# esp-lis3dh.net
KiCad netlist of a schematic drawn in EAGLE
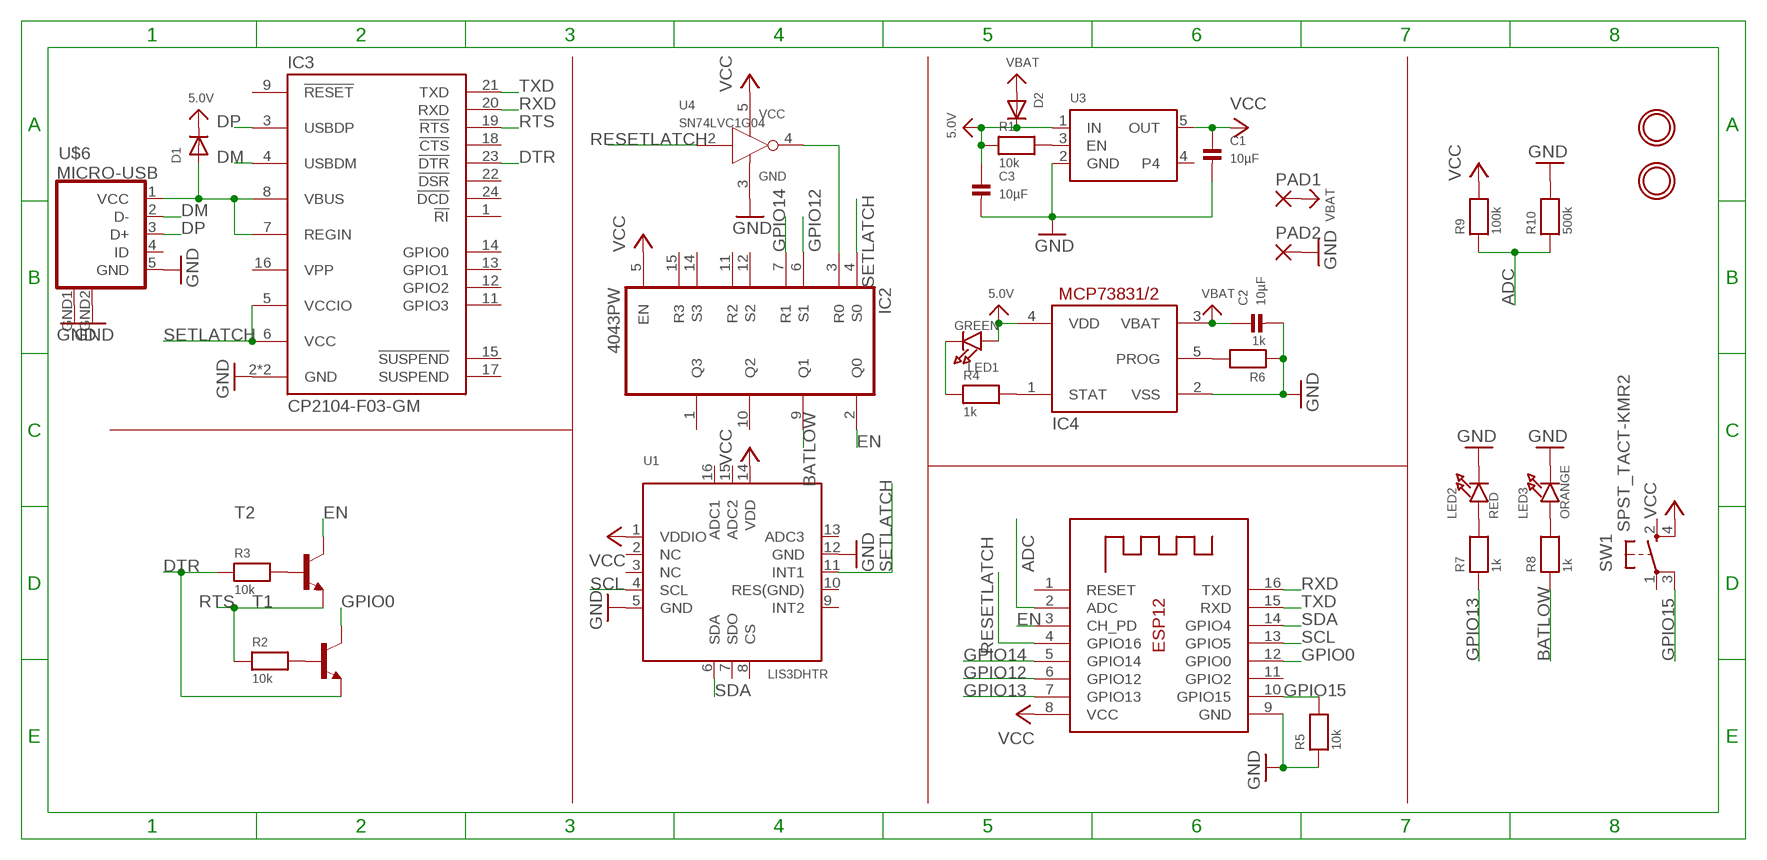
[diagram p0: schematic, sheet 1]

(export (version "E")
  (design (tool "Eeschema 10.0.6"))
  (components
    (comp (ref "C1")
      (value "10µF")
      (footprint "eagle-import:0805")
      (libsource (lib "eagle-import") (part "CAP_CERAMIC0805"))
    )
    (comp (ref "C2")
      (value "10µF")
      (footprint "eagle-import:0805")
      (libsource (lib "eagle-import") (part "CAP_CERAMIC0805"))
    )
    (comp (ref "C3")
      (value "10µF")
      (footprint "eagle-import:0805")
      (libsource (lib "eagle-import") (part "CAP_CERAMIC0805"))
    )
    (comp (ref "D1")
      (value "DIODESOD-123")
      (footprint "eagle-import:SOD-123")
      (libsource (lib "eagle-import") (part "DIODESOD-123"))
    )
    (comp (ref "D2")
      (value "DIODESOD-123")
      (footprint "eagle-import:SOD-123")
      (libsource (lib "eagle-import") (part "DIODESOD-123"))
    )
    (comp (ref "IC2")
      (value "4043PW")
      (footprint "eagle-import:TSSOP16")
      (libsource (lib "eagle-import") (part "4043PW"))
    )
    (comp (ref "IC3")
      (value "CP2104-F03-GM")
      (footprint "eagle-import:QFN24-PAD")
      (fields (field (name "MF") "Silicon Labs") (field (name "MP") "CP2104"))
      (libsource (lib "eagle-import") (part "CP2104-F03-GM"))
    )
    (comp (ref "IC4")
      (value "MCP73831/OT")
      (footprint "eagle-import:SOT23-5L")
      (libsource (lib "eagle-import") (part "MCP73831/OT"))
    )
    (comp (ref "LED1")
      (value "GREEN")
      (footprint "eagle-import:CHIPLED_0805")
      (libsource (lib "eagle-import") (part "LED0805"))
    )
    (comp (ref "LED2")
      (value "RED")
      (footprint "eagle-import:CHIPLED_0805")
      (libsource (lib "eagle-import") (part "LED0805"))
    )
    (comp (ref "LED3")
      (value "ORANGE")
      (footprint "eagle-import:CHIPLED_0805")
      (libsource (lib "eagle-import") (part "LED0805"))
    )
    (comp (ref "PAD1")
      (value "SMD2")
      (footprint "eagle-import:SMD1,27-2,54")
      (libsource (lib "eagle-import") (part "SMD2"))
    )
    (comp (ref "PAD2")
      (value "SMD2")
      (footprint "eagle-import:SMD1,27-2,54")
      (libsource (lib "eagle-import") (part "SMD2"))
    )
    (comp (ref "R1")
      (value "10k")
      (footprint "eagle-import:0603")
      (libsource (lib "eagle-import") (part "RESISTOR0603"))
    )
    (comp (ref "R2")
      (value "10k")
      (footprint "eagle-import:0603")
      (libsource (lib "eagle-import") (part "RESISTOR0603"))
    )
    (comp (ref "R3")
      (value "10k")
      (footprint "eagle-import:0603")
      (libsource (lib "eagle-import") (part "RESISTOR0603"))
    )
    (comp (ref "R4")
      (value "1k")
      (footprint "eagle-import:0603")
      (libsource (lib "eagle-import") (part "RESISTOR0603"))
    )
    (comp (ref "R5")
      (value "10k")
      (footprint "eagle-import:0603")
      (libsource (lib "eagle-import") (part "RESISTOR0603"))
    )
    (comp (ref "R6")
      (value "1k")
      (footprint "eagle-import:0603")
      (libsource (lib "eagle-import") (part "RESISTOR0603"))
    )
    (comp (ref "R7")
      (value "1k")
      (footprint "eagle-import:0603")
      (libsource (lib "eagle-import") (part "RESISTOR0603"))
    )
    (comp (ref "R8")
      (value "1k")
      (footprint "eagle-import:0603")
      (libsource (lib "eagle-import") (part "RESISTOR0603"))
    )
    (comp (ref "R9")
      (value "100k")
      (footprint "eagle-import:0603")
      (libsource (lib "eagle-import") (part "RESISTOR0603"))
    )
    (comp (ref "R10")
      (value "500k")
      (footprint "eagle-import:0603")
      (libsource (lib "eagle-import") (part "RESISTOR0603"))
    )
    (comp (ref "SW1")
      (value "SPST_TACT-KMR2")
      (footprint "eagle-import:KMR2")
      (libsource (lib "eagle-import") (part "SPST_TACT-KMR2"))
    )
    (comp (ref "T1")
      (value "MMBT2222ALT1-NPN-SOT23-BEC")
      (footprint "eagle-import:SOT23-BEC")
      (libsource (lib "eagle-import") (part "-NPN-SOT23-BECMMBT2222ALT1"))
    )
    (comp (ref "T2")
      (value "MMBT2222ALT1-NPN-SOT23-BEC")
      (footprint "eagle-import:SOT23-BEC")
      (libsource (lib "eagle-import") (part "-NPN-SOT23-BECMMBT2222ALT1"))
    )
    (comp (ref "U$6")
      (value "MICRO-USB")
      (footprint "eagle-import:MICRO-USB")
      (libsource (lib "eagle-import") (part "MICRO-USB"))
    )
    (comp (ref "U$7")
      (value "MOUNTINGHOLE2.5")
      (footprint "eagle-import:MOUNTINGHOLE_2.5_PLATED")
      (libsource (lib "eagle-import") (part "MOUNTINGHOLE2.5"))
    )
    (comp (ref "U$8")
      (value "MOUNTINGHOLE2.5")
      (footprint "eagle-import:MOUNTINGHOLE_2.5_PLATED")
      (libsource (lib "eagle-import") (part "MOUNTINGHOLE2.5"))
    )
    (comp (ref "U1")
      (value "LIS3DHTR")
      (footprint "eagle-import:LGA16_3X3MM")
      (libsource (lib "eagle-import") (part "ACCEL_LIS3DHTR"))
    )
    (comp (ref "U3")
      (value "VREG_SOT23-5")
      (footprint "eagle-import:SOT23-5")
      (libsource (lib "eagle-import") (part "VREG_SOT23-5"))
    )
    (comp (ref "U4")
      (value "SN74LVC1G04")
      (footprint "eagle-import:SOT23-5")
      (libsource (lib "eagle-import") (part "SN74LVC1G04"))
    )
    (comp (ref "X1")
      (value "ESP-12")
      (footprint "eagle-import:ESP-12")
      (libsource (lib "eagle-import") (part "ESP-12"))
    )
  )
  (nets
    (net (code "1") (name "/ADC") (class "Default")
      (node (ref "R10") (pin "1") (pinfunction "1_1") (pintype "passive"))
      (node (ref "R9") (pin "1") (pinfunction "1_1") (pintype "passive"))
      (node (ref "X1") (pin "2") (pinfunction "ADC_2") (pintype "passive"))
    )
    (net (code "2") (name "/BATLOW") (class "Default")
      (node (ref "IC2") (pin "9") (pinfunction "Q1_9") (pintype "output"))
      (node (ref "R8") (pin "1") (pinfunction "1_1") (pintype "passive"))
    )
    (net (code "3") (name "/DM") (class "Default")
      (node (ref "IC3") (pin "4") (pinfunction "USBDM_4") (pintype "bidirectional"))
      (node (ref "U$6") (pin "2") (pinfunction "D-_2") (pintype "bidirectional"))
    )
    (net (code "4") (name "/DP") (class "Default")
      (node (ref "IC3") (pin "3") (pinfunction "USBDP_3") (pintype "bidirectional"))
      (node (ref "U$6") (pin "3") (pinfunction "D+_3") (pintype "bidirectional"))
    )
    (net (code "5") (name "/DTR") (class "Default")
      (node (ref "IC3") (pin "23") (pinfunction "~{DTR}_23") (pintype "bidirectional"))
      (node (ref "R3") (pin "1") (pinfunction "1_1") (pintype "passive"))
      (node (ref "T1") (pin "E") (pinfunction "E_E") (pintype "passive"))
    )
    (net (code "6") (name "/EN") (class "Default")
      (node (ref "IC2") (pin "2") (pinfunction "Q0_2") (pintype "output"))
      (node (ref "T2") (pin "C") (pinfunction "C_C") (pintype "passive"))
      (node (ref "X1") (pin "3") (pinfunction "CH_PD_3") (pintype "input"))
    )
    (net (code "7") (name "/GPIO0") (class "Default")
      (node (ref "T1") (pin "C") (pinfunction "C_C") (pintype "passive"))
      (node (ref "X1") (pin "12") (pinfunction "GPIO0_12") (pintype "bidirectional"))
    )
    (net (code "8") (name "/GPIO12") (class "Default")
      (node (ref "IC2") (pin "6") (pinfunction "S1_6") (pintype "input"))
      (node (ref "X1") (pin "6") (pinfunction "GPIO12_6") (pintype "bidirectional"))
    )
    (net (code "9") (name "/GPIO13") (class "Default")
      (node (ref "R7") (pin "1") (pinfunction "1_1") (pintype "passive"))
      (node (ref "X1") (pin "7") (pinfunction "GPIO13_7") (pintype "bidirectional"))
    )
    (net (code "10") (name "/GPIO14") (class "Default")
      (node (ref "IC2") (pin "7") (pinfunction "R1_7") (pintype "input"))
      (node (ref "X1") (pin "5") (pinfunction "GPIO14_5") (pintype "bidirectional"))
    )
    (net (code "11") (name "/GPIO15") (class "Default")
      (node (ref "R5") (pin "2") (pinfunction "2_2") (pintype "passive"))
      (node (ref "SW1") (pin "3") (pinfunction "P1_3") (pintype "passive"))
      (node (ref "X1") (pin "10") (pinfunction "GPIO15_10") (pintype "bidirectional"))
    )
    (net (code "12") (name "/RESETLATCH") (class "Default")
      (node (ref "U4") (pin "2") (pinfunction "A_2") (pintype "bidirectional"))
      (node (ref "X1") (pin "4") (pinfunction "GPIO16_4") (pintype "bidirectional"))
    )
    (net (code "13") (name "/RTS") (class "Default")
      (node (ref "IC3") (pin "19") (pinfunction "~{RTS}_19") (pintype "bidirectional"))
      (node (ref "R2") (pin "1") (pinfunction "1_1") (pintype "passive"))
      (node (ref "T2") (pin "E") (pinfunction "E_E") (pintype "passive"))
    )
    (net (code "14") (name "/RXD") (class "Default")
      (node (ref "IC3") (pin "20") (pinfunction "RXD_20") (pintype "bidirectional"))
      (node (ref "X1") (pin "16") (pinfunction "TXD_16") (pintype "output"))
    )
    (net (code "15") (name "/SCL") (class "Default")
      (node (ref "U1") (pin "4") (pinfunction "SCL_4") (pintype "bidirectional"))
      (node (ref "X1") (pin "13") (pinfunction "GPIO5_13") (pintype "bidirectional"))
    )
    (net (code "16") (name "/SDA") (class "Default")
      (node (ref "U1") (pin "6") (pinfunction "SDA_6") (pintype "bidirectional"))
      (node (ref "X1") (pin "14") (pinfunction "GPIO4_14") (pintype "bidirectional"))
    )
    (net (code "17") (name "/SETLATCH") (class "Default")
      (node (ref "IC2") (pin "4") (pinfunction "S0_4") (pintype "input"))
      (node (ref "IC3") (pin "5") (pinfunction "VCCIO_5") (pintype "power_in"))
      (node (ref "IC3") (pin "6") (pinfunction "VCC_6") (pintype "power_in"))
      (node (ref "U1") (pin "11") (pinfunction "INT1_11") (pintype "output"))
    )
    (net (code "18") (name "/TXD") (class "Default")
      (node (ref "IC3") (pin "21") (pinfunction "TXD_21") (pintype "bidirectional"))
      (node (ref "X1") (pin "15") (pinfunction "RXD_15") (pintype "input"))
    )
    (net (code "19") (name "/VPP") (class "Default")
      (node (ref "IC3") (pin "16") (pinfunction "VPP_16") (pintype "power_in"))
    )
    (net (code "20") (name "5.0V") (class "Default")
      (node (ref "C3") (pin "1") (pinfunction "P$1_1") (pintype "passive"))
      (node (ref "D1") (pin "C") (pinfunction "C_C") (pintype "passive"))
      (node (ref "D2") (pin "C") (pinfunction "C_C") (pintype "passive"))
      (node (ref "IC4") (pin "4") (pinfunction "VDD_4") (pintype "power_in"))
      (node (ref "LED1") (pin "A") (pinfunction "A_A") (pintype "passive"))
      (node (ref "R1") (pin "1") (pinfunction "1_1") (pintype "passive"))
      (node (ref "U3") (pin "1") (pinfunction "IN_1") (pintype "bidirectional"))
    )
    (net (code "21") (name "GND") (class "Default")
      (node (ref "C1") (pin "2") (pinfunction "P$2_2") (pintype "passive"))
      (node (ref "C2") (pin "2") (pinfunction "P$2_2") (pintype "passive"))
      (node (ref "C3") (pin "2") (pinfunction "P$2_2") (pintype "passive"))
      (node (ref "IC3") (pin "2") (pinfunction "GND_2") (pintype "power_in"))
      (node (ref "IC3") (pin "TP") (pinfunction "GND_TP") (pintype "power_in"))
      (node (ref "IC4") (pin "2") (pinfunction "VSS_2") (pintype "power_in"))
      (node (ref "LED2") (pin "C") (pinfunction "C_C") (pintype "passive"))
      (node (ref "LED3") (pin "C") (pinfunction "C_C") (pintype "passive"))
      (node (ref "PAD2") (pin "1") (pinfunction "P_1") (pintype "passive"))
      (node (ref "R10") (pin "2") (pinfunction "2_2") (pintype "passive"))
      (node (ref "R5") (pin "1") (pinfunction "1_1") (pintype "passive"))
      (node (ref "R6") (pin "1") (pinfunction "1_1") (pintype "passive"))
      (node (ref "U$6") (pin "5") (pinfunction "GND_5") (pintype "power_in"))
      (node (ref "U$6") (pin "GND1") (pinfunction "GND_GND1") (pintype "power_in"))
      (node (ref "U$6") (pin "GND2") (pinfunction "GND_GND2") (pintype "power_in"))
      (node (ref "U1") (pin "12") (pinfunction "GND_12") (pintype "power_in"))
      (node (ref "U1") (pin "5") (pinfunction "GND_5") (pintype "power_in"))
      (node (ref "U3") (pin "2") (pinfunction "GND_2") (pintype "bidirectional"))
      (node (ref "U4") (pin "3") (pinfunction "GND_3") (pintype "bidirectional"))
      (node (ref "X1") (pin "9") (pinfunction "GND_9") (pintype "power_in"))
    )
    (net (code "22") (name "Net-(IC2A-R0)") (class "Default")
      (node (ref "IC2") (pin "3") (pinfunction "R0_3") (pintype "input"))
      (node (ref "U4") (pin "4") (pinfunction "Y_4") (pintype "bidirectional"))
    )
    (net (code "23") (name "Net-(IC3-REGIN)") (class "Default")
      (node (ref "D1") (pin "A") (pinfunction "A_A") (pintype "passive"))
      (node (ref "IC3") (pin "7") (pinfunction "REGIN_7") (pintype "power_in"))
      (node (ref "IC3") (pin "8") (pinfunction "VBUS_8") (pintype "power_in"))
      (node (ref "U$6") (pin "1") (pinfunction "VCC_1") (pintype "power_in"))
    )
    (net (code "24") (name "Net-(IC4-PROG)") (class "Default")
      (node (ref "IC4") (pin "5") (pinfunction "PROG_5") (pintype "input"))
      (node (ref "R6") (pin "2") (pinfunction "2_2") (pintype "passive"))
    )
    (net (code "25") (name "Net-(IC4-STAT)") (class "Default")
      (node (ref "IC4") (pin "1") (pinfunction "STAT_1") (pintype "output"))
      (node (ref "R4") (pin "2") (pinfunction "2_2") (pintype "passive"))
    )
    (net (code "26") (name "Net-(LED1-PadC)") (class "Default")
      (node (ref "LED1") (pin "C") (pinfunction "C_C") (pintype "passive"))
      (node (ref "R4") (pin "1") (pinfunction "1_1") (pintype "passive"))
    )
    (net (code "27") (name "Net-(LED2-PadA)") (class "Default")
      (node (ref "LED2") (pin "A") (pinfunction "A_A") (pintype "passive"))
      (node (ref "R7") (pin "2") (pinfunction "2_2") (pintype "passive"))
    )
    (net (code "28") (name "Net-(LED3-PadA)") (class "Default")
      (node (ref "LED3") (pin "A") (pinfunction "A_A") (pintype "passive"))
      (node (ref "R8") (pin "2") (pinfunction "2_2") (pintype "passive"))
    )
    (net (code "29") (name "Net-(R2-Pad2)") (class "Default")
      (node (ref "R2") (pin "2") (pinfunction "2_2") (pintype "passive"))
      (node (ref "T1") (pin "B") (pinfunction "B_B") (pintype "passive"))
    )
    (net (code "30") (name "Net-(R3-Pad2)") (class "Default")
      (node (ref "R3") (pin "2") (pinfunction "2_2") (pintype "passive"))
      (node (ref "T2") (pin "B") (pinfunction "B_B") (pintype "passive"))
    )
    (net (code "31") (name "Net-(U3-EN)") (class "Default")
      (node (ref "R1") (pin "2") (pinfunction "2_2") (pintype "passive"))
      (node (ref "U3") (pin "3") (pinfunction "EN_3") (pintype "bidirectional"))
    )
    (net (code "32") (name "VBAT") (class "Default")
      (node (ref "C2") (pin "1") (pinfunction "P$1_1") (pintype "passive"))
      (node (ref "D2") (pin "A") (pinfunction "A_A") (pintype "passive"))
      (node (ref "IC4") (pin "3") (pinfunction "VBAT_3") (pintype "bidirectional"))
      (node (ref "PAD1") (pin "1") (pinfunction "P_1") (pintype "passive"))
    )
    (net (code "33") (name "VCC") (class "Default")
      (node (ref "C1") (pin "1") (pinfunction "P$1_1") (pintype "passive"))
      (node (ref "IC2") (pin "5") (pinfunction "EN_5") (pintype "input"))
      (node (ref "R9") (pin "2") (pinfunction "2_2") (pintype "passive"))
      (node (ref "SW1") (pin "4") (pinfunction "S1_4") (pintype "passive"))
      (node (ref "U1") (pin "1") (pinfunction "VDDIO_1") (pintype "power_in"))
      (node (ref "U1") (pin "14") (pinfunction "VDD_14") (pintype "power_in"))
      (node (ref "U3") (pin "5") (pinfunction "OUT_5") (pintype "bidirectional"))
      (node (ref "U4") (pin "5") (pinfunction "VCC_5") (pintype "bidirectional"))
      (node (ref "X1") (pin "8") (pinfunction "VCC_8") (pintype "power_in"))
    )
    (net (code "34") (name "unconnected-(IC2A-Q2-Pad10)") (class "Default")
      (node (ref "IC2") (pin "10") (pinfunction "Q2_10") (pintype "output"))
    )
    (net (code "35") (name "unconnected-(IC2A-Q3-Pad1)") (class "Default")
      (node (ref "IC2") (pin "1") (pinfunction "Q3_1") (pintype "output"))
    )
    (net (code "36") (name "unconnected-(IC2A-R2-Pad11)") (class "Default")
      (node (ref "IC2") (pin "11") (pinfunction "R2_11") (pintype "input"))
    )
    (net (code "37") (name "unconnected-(IC2A-R3-Pad15)") (class "Default")
      (node (ref "IC2") (pin "15") (pinfunction "R3_15") (pintype "input"))
    )
    (net (code "38") (name "unconnected-(IC2A-S2-Pad12)") (class "Default")
      (node (ref "IC2") (pin "12") (pinfunction "S2_12") (pintype "input"))
    )
    (net (code "39") (name "unconnected-(IC2A-S3-Pad14)") (class "Default")
      (node (ref "IC2") (pin "14") (pinfunction "S3_14") (pintype "input"))
    )
    (net (code "40") (name "unconnected-(IC3-GPIO0-Pad14)") (class "Default")
      (node (ref "IC3") (pin "14") (pinfunction "GPIO0_14") (pintype "bidirectional"))
    )
    (net (code "41") (name "unconnected-(IC3-GPIO1-Pad13)") (class "Default")
      (node (ref "IC3") (pin "13") (pinfunction "GPIO1_13") (pintype "bidirectional"))
    )
    (net (code "42") (name "unconnected-(IC3-GPIO2-Pad12)") (class "Default")
      (node (ref "IC3") (pin "12") (pinfunction "GPIO2_12") (pintype "bidirectional"))
    )
    (net (code "43") (name "unconnected-(IC3-GPIO3-Pad11)") (class "Default")
      (node (ref "IC3") (pin "11") (pinfunction "GPIO3_11") (pintype "bidirectional"))
    )
    (net (code "44") (name "unconnected-(IC3-SUSPEND-Pad17)") (class "Default")
      (node (ref "IC3") (pin "17") (pinfunction "SUSPEND_17") (pintype "bidirectional"))
    )
    (net (code "45") (name "unconnected-(IC3-~{CTS}-Pad18)") (class "Default")
      (node (ref "IC3") (pin "18") (pinfunction "~{CTS}_18") (pintype "bidirectional"))
    )
    (net (code "46") (name "unconnected-(IC3-~{DCD}-Pad24)") (class "Default")
      (node (ref "IC3") (pin "24") (pinfunction "~{DCD}_24") (pintype "bidirectional"))
    )
    (net (code "47") (name "unconnected-(IC3-~{DSR}-Pad22)") (class "Default")
      (node (ref "IC3") (pin "22") (pinfunction "~{DSR}_22") (pintype "bidirectional"))
    )
    (net (code "48") (name "unconnected-(IC3-~{RESET}-Pad9)") (class "Default")
      (node (ref "IC3") (pin "9") (pinfunction "~{RESET}_9") (pintype "bidirectional"))
    )
    (net (code "49") (name "unconnected-(IC3-~{RI}-Pad1)") (class "Default")
      (node (ref "IC3") (pin "1") (pinfunction "~{RI}_1") (pintype "bidirectional"))
    )
    (net (code "50") (name "unconnected-(IC3-~{SUSPEND}-Pad15)") (class "Default")
      (node (ref "IC3") (pin "15") (pinfunction "~{SUSPEND}_15") (pintype "bidirectional"))
    )
    (net (code "51") (name "unconnected-(SW1-P-Pad1)") (class "Default")
      (node (ref "SW1") (pin "1") (pinfunction "P_1") (pintype "passive"))
    )
    (net (code "52") (name "unconnected-(SW1-S-Pad2)") (class "Default")
      (node (ref "SW1") (pin "2") (pinfunction "S_2") (pintype "passive"))
    )
    (net (code "53") (name "unconnected-(U$6-ID-Pad4)") (class "Default")
      (node (ref "U$6") (pin "4") (pinfunction "ID_4") (pintype "bidirectional"))
    )
    (net (code "54") (name "unconnected-(U1-ADC1-Pad16)") (class "Default")
      (node (ref "U1") (pin "16") (pinfunction "ADC1_16") (pintype "input"))
    )
    (net (code "55") (name "unconnected-(U1-ADC2-Pad15)") (class "Default")
      (node (ref "U1") (pin "15") (pinfunction "ADC2_15") (pintype "input"))
    )
    (net (code "56") (name "unconnected-(U1-ADC3-Pad13)") (class "Default")
      (node (ref "U1") (pin "13") (pinfunction "ADC3_13") (pintype "input"))
    )
    (net (code "57") (name "unconnected-(U1-CS-Pad8)") (class "Default")
      (node (ref "U1") (pin "8") (pinfunction "CS_8") (pintype "input"))
    )
    (net (code "58") (name "unconnected-(U1-INT2-Pad9)") (class "Default")
      (node (ref "U1") (pin "9") (pinfunction "INT2_9") (pintype "output"))
    )
    (net (code "59") (name "unconnected-(U1-NC-Pad2)") (class "Default")
      (node (ref "U1") (pin "2") (pinfunction "NC_2") (pintype "no_connect"))
    )
    (net (code "60") (name "unconnected-(U1-NC-Pad3)") (class "Default")
      (node (ref "U1") (pin "3") (pinfunction "NC_3") (pintype "no_connect"))
    )
    (net (code "61") (name "unconnected-(U1-RES(GND)-Pad10)") (class "Default")
      (node (ref "U1") (pin "10") (pinfunction "RES(GND)_10") (pintype "bidirectional"))
    )
    (net (code "62") (name "unconnected-(U1-SDO-Pad7)") (class "Default")
      (node (ref "U1") (pin "7") (pinfunction "SDO_7") (pintype "bidirectional"))
    )
    (net (code "63") (name "unconnected-(U3-P4-Pad4)") (class "Default")
      (node (ref "U3") (pin "4") (pinfunction "P4_4") (pintype "bidirectional"))
    )
    (net (code "64") (name "unconnected-(X1-GPIO2-Pad11)") (class "Default")
      (node (ref "X1") (pin "11") (pinfunction "GPIO2_11") (pintype "bidirectional"))
    )
    (net (code "65") (name "unconnected-(X1-RESET-Pad1)") (class "Default")
      (node (ref "X1") (pin "1") (pinfunction "RESET_1") (pintype "input"))
    )
  )
)
